# FEU-102-1_part3.net
KiCad netlist of a schematic drawn in Altium Designer
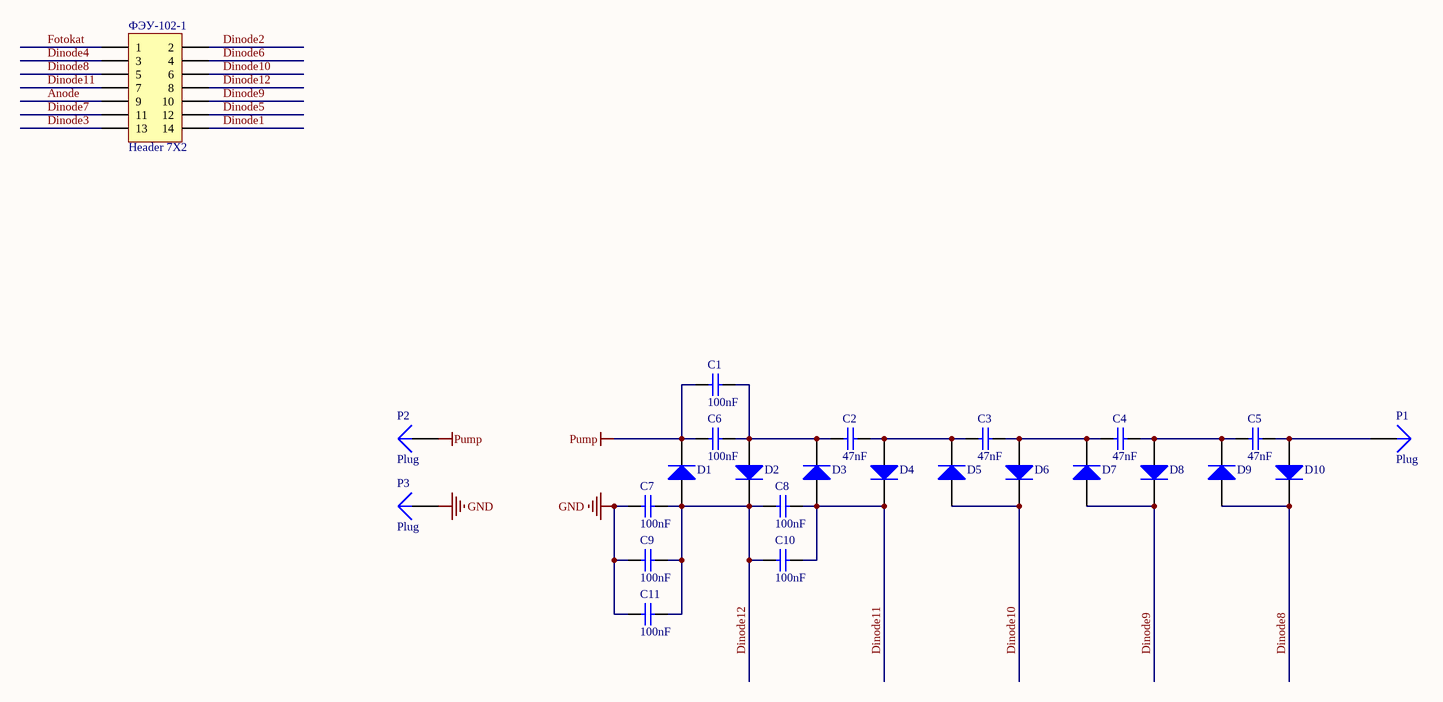
[diagram p0: FEU-102-1_part3.SchDoc]

(export (version "E")
  (design (tool "Eeschema 10.0.6"))
  (components
    (comp (ref "C1")
      (value "100nF")
      (footprint "Miscellaneous Devices:C1206")
      (description "Capacitor (Semiconductor SIM Model)")
      (fields (field (name "PUBLISHER") "Altium Limited"))
      (libsource (lib "Miscellaneous Devices") (part "Cap Semi"))
    )
    (comp (ref "C2")
      (value "47nF")
      (footprint "0805_CAP")
      (description "Capacitor (Semiconductor SIM Model)")
      (fields (field (name "PUBLISHER") "Altium Limited"))
      (libsource (lib "Miscellaneous Devices") (part "Cap Semi"))
    )
    (comp (ref "C3")
      (value "47nF")
      (footprint "0805_CAP")
      (description "Capacitor (Semiconductor SIM Model)")
      (fields (field (name "PUBLISHER") "Altium Limited"))
      (libsource (lib "Miscellaneous Devices") (part "Cap Semi"))
    )
    (comp (ref "C4")
      (value "47nF")
      (footprint "0805_CAP")
      (description "Capacitor (Semiconductor SIM Model)")
      (fields (field (name "PUBLISHER") "Altium Limited"))
      (libsource (lib "Miscellaneous Devices") (part "Cap Semi"))
    )
    (comp (ref "C5")
      (value "47nF")
      (footprint "0805_CAP")
      (description "Capacitor (Semiconductor SIM Model)")
      (fields (field (name "PUBLISHER") "Altium Limited"))
      (libsource (lib "Miscellaneous Devices") (part "Cap Semi"))
    )
    (comp (ref "C6")
      (value "100nF")
      (footprint "Miscellaneous Devices:C1206")
      (description "Capacitor (Semiconductor SIM Model)")
      (fields (field (name "PUBLISHER") "Altium Limited"))
      (libsource (lib "Miscellaneous Devices") (part "Cap Semi"))
    )
    (comp (ref "C7")
      (value "100nF")
      (footprint "Miscellaneous Devices:C1206")
      (description "Capacitor (Semiconductor SIM Model)")
      (fields (field (name "PUBLISHER") "Altium Limited"))
      (libsource (lib "Miscellaneous Devices") (part "Cap Semi"))
    )
    (comp (ref "C8")
      (value "100nF")
      (footprint "Miscellaneous Devices:C1206")
      (description "Capacitor (Semiconductor SIM Model)")
      (fields (field (name "PUBLISHER") "Altium Limited"))
      (libsource (lib "Miscellaneous Devices") (part "Cap Semi"))
    )
    (comp (ref "C9")
      (value "100nF")
      (footprint "Miscellaneous Devices:C1206")
      (description "Capacitor (Semiconductor SIM Model)")
      (fields (field (name "PUBLISHER") "Altium Limited"))
      (libsource (lib "Miscellaneous Devices") (part "Cap Semi"))
    )
    (comp (ref "C10")
      (value "100nF")
      (footprint "Miscellaneous Devices:C1206")
      (description "Capacitor (Semiconductor SIM Model)")
      (fields (field (name "PUBLISHER") "Altium Limited"))
      (libsource (lib "Miscellaneous Devices") (part "Cap Semi"))
    )
    (comp (ref "C11")
      (value "100nF")
      (footprint "Miscellaneous Devices:C1206")
      (description "Capacitor (Semiconductor SIM Model)")
      (fields (field (name "PUBLISHER") "Altium Limited"))
      (libsource (lib "Miscellaneous Devices") (part "Cap Semi"))
    )
    (comp (ref "D1")
      (value "~")
      (footprint "DA2JF8100L")
      (description "Default Diode")
      (fields (field (name "PUBLISHER") "Altium Limited"))
      (libsource (lib "Miscellaneous Devices") (part "Diode"))
    )
    (comp (ref "D2")
      (value "~")
      (footprint "DA2JF8100L")
      (description "Default Diode")
      (fields (field (name "PUBLISHER") "Altium Limited"))
      (libsource (lib "Miscellaneous Devices") (part "Diode"))
    )
    (comp (ref "D3")
      (value "~")
      (footprint "DA2JF8100L")
      (description "Default Diode")
      (fields (field (name "PUBLISHER") "Altium Limited"))
      (libsource (lib "Miscellaneous Devices") (part "Diode"))
    )
    (comp (ref "D4")
      (value "~")
      (footprint "DA2JF8100L")
      (description "Default Diode")
      (fields (field (name "PUBLISHER") "Altium Limited"))
      (libsource (lib "Miscellaneous Devices") (part "Diode"))
    )
    (comp (ref "D5")
      (value "~")
      (footprint "DA2JF8100L")
      (description "Default Diode")
      (fields (field (name "PUBLISHER") "Altium Limited"))
      (libsource (lib "Miscellaneous Devices") (part "Diode"))
    )
    (comp (ref "D6")
      (value "~")
      (footprint "DA2JF8100L")
      (description "Default Diode")
      (fields (field (name "PUBLISHER") "Altium Limited"))
      (libsource (lib "Miscellaneous Devices") (part "Diode"))
    )
    (comp (ref "D7")
      (value "~")
      (footprint "DA2JF8100L")
      (description "Default Diode")
      (fields (field (name "PUBLISHER") "Altium Limited"))
      (libsource (lib "Miscellaneous Devices") (part "Diode"))
    )
    (comp (ref "D8")
      (value "~")
      (footprint "DA2JF8100L")
      (description "Default Diode")
      (fields (field (name "PUBLISHER") "Altium Limited"))
      (libsource (lib "Miscellaneous Devices") (part "Diode"))
    )
    (comp (ref "D9")
      (value "~")
      (footprint "DA2JF8100L")
      (description "Default Diode")
      (fields (field (name "PUBLISHER") "Altium Limited"))
      (libsource (lib "Miscellaneous Devices") (part "Diode"))
    )
    (comp (ref "D10")
      (value "~")
      (footprint "DA2JF8100L")
      (description "Default Diode")
      (fields (field (name "PUBLISHER") "Altium Limited"))
      (libsource (lib "Miscellaneous Devices") (part "Diode"))
    )
    (comp (ref "P1")
      (value "Plug")
      (footprint "PIN1")
      (fields (field (name "PUBLISHER") "Altium Limited"))
      (libsource (lib "Miscellaneous Connectors") (part "Plug"))
    )
    (comp (ref "P2")
      (value "Plug")
      (footprint "PIN1")
      (fields (field (name "PUBLISHER") "Altium Limited"))
      (libsource (lib "Miscellaneous Connectors") (part "Plug"))
    )
    (comp (ref "P3")
      (value "Plug")
      (footprint "PIN1")
      (fields (field (name "PUBLISHER") "Altium Limited"))
      (libsource (lib "Miscellaneous Connectors") (part "Plug"))
    )
    (comp (ref "ФЭУ-102-1")
      (value "Header 7X2")
      (footprint "ФЭУ-102")
      (description "Header, 7-Pin, Dual row")
      (fields (field (name "PUBLISHER") "Altium Limited"))
      (libsource (lib "Miscellaneous Connectors") (part "Header 7X2"))
    )
  )
  (nets
    (net (code "1") (name "/Anode") (class "Default")
      (node (ref "ФЭУ-102-1") (pin "9") (pinfunction "9_9") (pintype "passive"))
    )
    (net (code "2") (name "/Dinode1") (class "Default")
      (node (ref "ФЭУ-102-1") (pin "14") (pinfunction "14_14") (pintype "passive"))
    )
    (net (code "3") (name "/Dinode2") (class "Default")
      (node (ref "ФЭУ-102-1") (pin "2") (pinfunction "2_2") (pintype "passive"))
    )
    (net (code "4") (name "/Dinode3") (class "Default")
      (node (ref "ФЭУ-102-1") (pin "13") (pinfunction "13_13") (pintype "passive"))
    )
    (net (code "5") (name "/Dinode4") (class "Default")
      (node (ref "ФЭУ-102-1") (pin "3") (pinfunction "3_3") (pintype "passive"))
    )
    (net (code "6") (name "/Dinode5") (class "Default")
      (node (ref "ФЭУ-102-1") (pin "12") (pinfunction "12_12") (pintype "passive"))
    )
    (net (code "7") (name "/Dinode6") (class "Default")
      (node (ref "ФЭУ-102-1") (pin "4") (pinfunction "4_4") (pintype "passive"))
    )
    (net (code "8") (name "/Dinode7") (class "Default")
      (node (ref "ФЭУ-102-1") (pin "11") (pinfunction "11_11") (pintype "passive"))
    )
    (net (code "9") (name "/Dinode8") (class "Default")
      (node (ref "D10") (pin "2") (pinfunction "K_2") (pintype "passive"))
      (node (ref "D9") (pin "1") (pinfunction "A_1") (pintype "passive"))
      (node (ref "ФЭУ-102-1") (pin "5") (pinfunction "5_5") (pintype "passive"))
    )
    (net (code "10") (name "/Dinode9") (class "Default")
      (node (ref "D7") (pin "1") (pinfunction "A_1") (pintype "passive"))
      (node (ref "D8") (pin "2") (pinfunction "K_2") (pintype "passive"))
      (node (ref "ФЭУ-102-1") (pin "10") (pinfunction "10_10") (pintype "passive"))
    )
    (net (code "11") (name "/Dinode10") (class "Default")
      (node (ref "D5") (pin "1") (pinfunction "A_1") (pintype "passive"))
      (node (ref "D6") (pin "2") (pinfunction "K_2") (pintype "passive"))
      (node (ref "ФЭУ-102-1") (pin "6") (pinfunction "6_6") (pintype "passive"))
    )
    (net (code "12") (name "/Dinode11") (class "Default")
      (node (ref "C10") (pin "1") (pinfunction "1_1") (pintype "passive"))
      (node (ref "C8") (pin "1") (pinfunction "1_1") (pintype "passive"))
      (node (ref "D3") (pin "1") (pinfunction "A_1") (pintype "passive"))
      (node (ref "D4") (pin "2") (pinfunction "K_2") (pintype "passive"))
      (node (ref "ФЭУ-102-1") (pin "7") (pinfunction "7_7") (pintype "passive"))
    )
    (net (code "13") (name "/Dinode12") (class "Default")
      (node (ref "C10") (pin "2") (pinfunction "2_2") (pintype "passive"))
      (node (ref "C11") (pin "1") (pinfunction "1_1") (pintype "passive"))
      (node (ref "C7") (pin "1") (pinfunction "1_1") (pintype "passive"))
      (node (ref "C8") (pin "2") (pinfunction "2_2") (pintype "passive"))
      (node (ref "C9") (pin "1") (pinfunction "1_1") (pintype "passive"))
      (node (ref "D1") (pin "1") (pinfunction "A_1") (pintype "passive"))
      (node (ref "D2") (pin "2") (pinfunction "K_2") (pintype "passive"))
      (node (ref "ФЭУ-102-1") (pin "8") (pinfunction "8_8") (pintype "passive"))
    )
    (net (code "14") (name "/Fotokat") (class "Default")
      (node (ref "ФЭУ-102-1") (pin "1") (pinfunction "1_1") (pintype "passive"))
    )
    (net (code "15") (name "GND") (class "Default")
      (node (ref "C11") (pin "2") (pinfunction "2_2") (pintype "passive"))
      (node (ref "C7") (pin "2") (pinfunction "2_2") (pintype "passive"))
      (node (ref "C9") (pin "2") (pinfunction "2_2") (pintype "passive"))
      (node (ref "P3") (pin "1") (pinfunction "1_1") (pintype "passive"))
    )
    (net (code "16") (name "Net-(D2-A)") (class "Default")
      (node (ref "C1") (pin "1") (pinfunction "1_1") (pintype "passive"))
      (node (ref "C2") (pin "2") (pinfunction "2_2") (pintype "passive"))
      (node (ref "C6") (pin "1") (pinfunction "1_1") (pintype "passive"))
      (node (ref "D2") (pin "1") (pinfunction "A_1") (pintype "passive"))
      (node (ref "D3") (pin "2") (pinfunction "K_2") (pintype "passive"))
    )
    (net (code "17") (name "Net-(D4-A)") (class "Default")
      (node (ref "C2") (pin "1") (pinfunction "1_1") (pintype "passive"))
      (node (ref "C3") (pin "2") (pinfunction "2_2") (pintype "passive"))
      (node (ref "D4") (pin "1") (pinfunction "A_1") (pintype "passive"))
      (node (ref "D5") (pin "2") (pinfunction "K_2") (pintype "passive"))
    )
    (net (code "18") (name "Net-(D6-A)") (class "Default")
      (node (ref "C3") (pin "1") (pinfunction "1_1") (pintype "passive"))
      (node (ref "C4") (pin "2") (pinfunction "2_2") (pintype "passive"))
      (node (ref "D6") (pin "1") (pinfunction "A_1") (pintype "passive"))
      (node (ref "D7") (pin "2") (pinfunction "K_2") (pintype "passive"))
    )
    (net (code "19") (name "Net-(D8-A)") (class "Default")
      (node (ref "C4") (pin "1") (pinfunction "1_1") (pintype "passive"))
      (node (ref "C5") (pin "2") (pinfunction "2_2") (pintype "passive"))
      (node (ref "D8") (pin "1") (pinfunction "A_1") (pintype "passive"))
      (node (ref "D9") (pin "2") (pinfunction "K_2") (pintype "passive"))
    )
    (net (code "20") (name "Net-(D10-A)") (class "Default")
      (node (ref "C5") (pin "1") (pinfunction "1_1") (pintype "passive"))
      (node (ref "D10") (pin "1") (pinfunction "A_1") (pintype "passive"))
      (node (ref "P1") (pin "1") (pinfunction "1_1") (pintype "passive"))
    )
    (net (code "21") (name "Pump") (class "Default")
      (node (ref "C1") (pin "2") (pinfunction "2_2") (pintype "passive"))
      (node (ref "C6") (pin "2") (pinfunction "2_2") (pintype "passive"))
      (node (ref "D1") (pin "2") (pinfunction "K_2") (pintype "passive"))
      (node (ref "P2") (pin "1") (pinfunction "1_1") (pintype "passive"))
    )
  )
)
